# SparkFun_TEMT6000_Breakout-v12.net
KiCad netlist of a schematic drawn in EAGLE
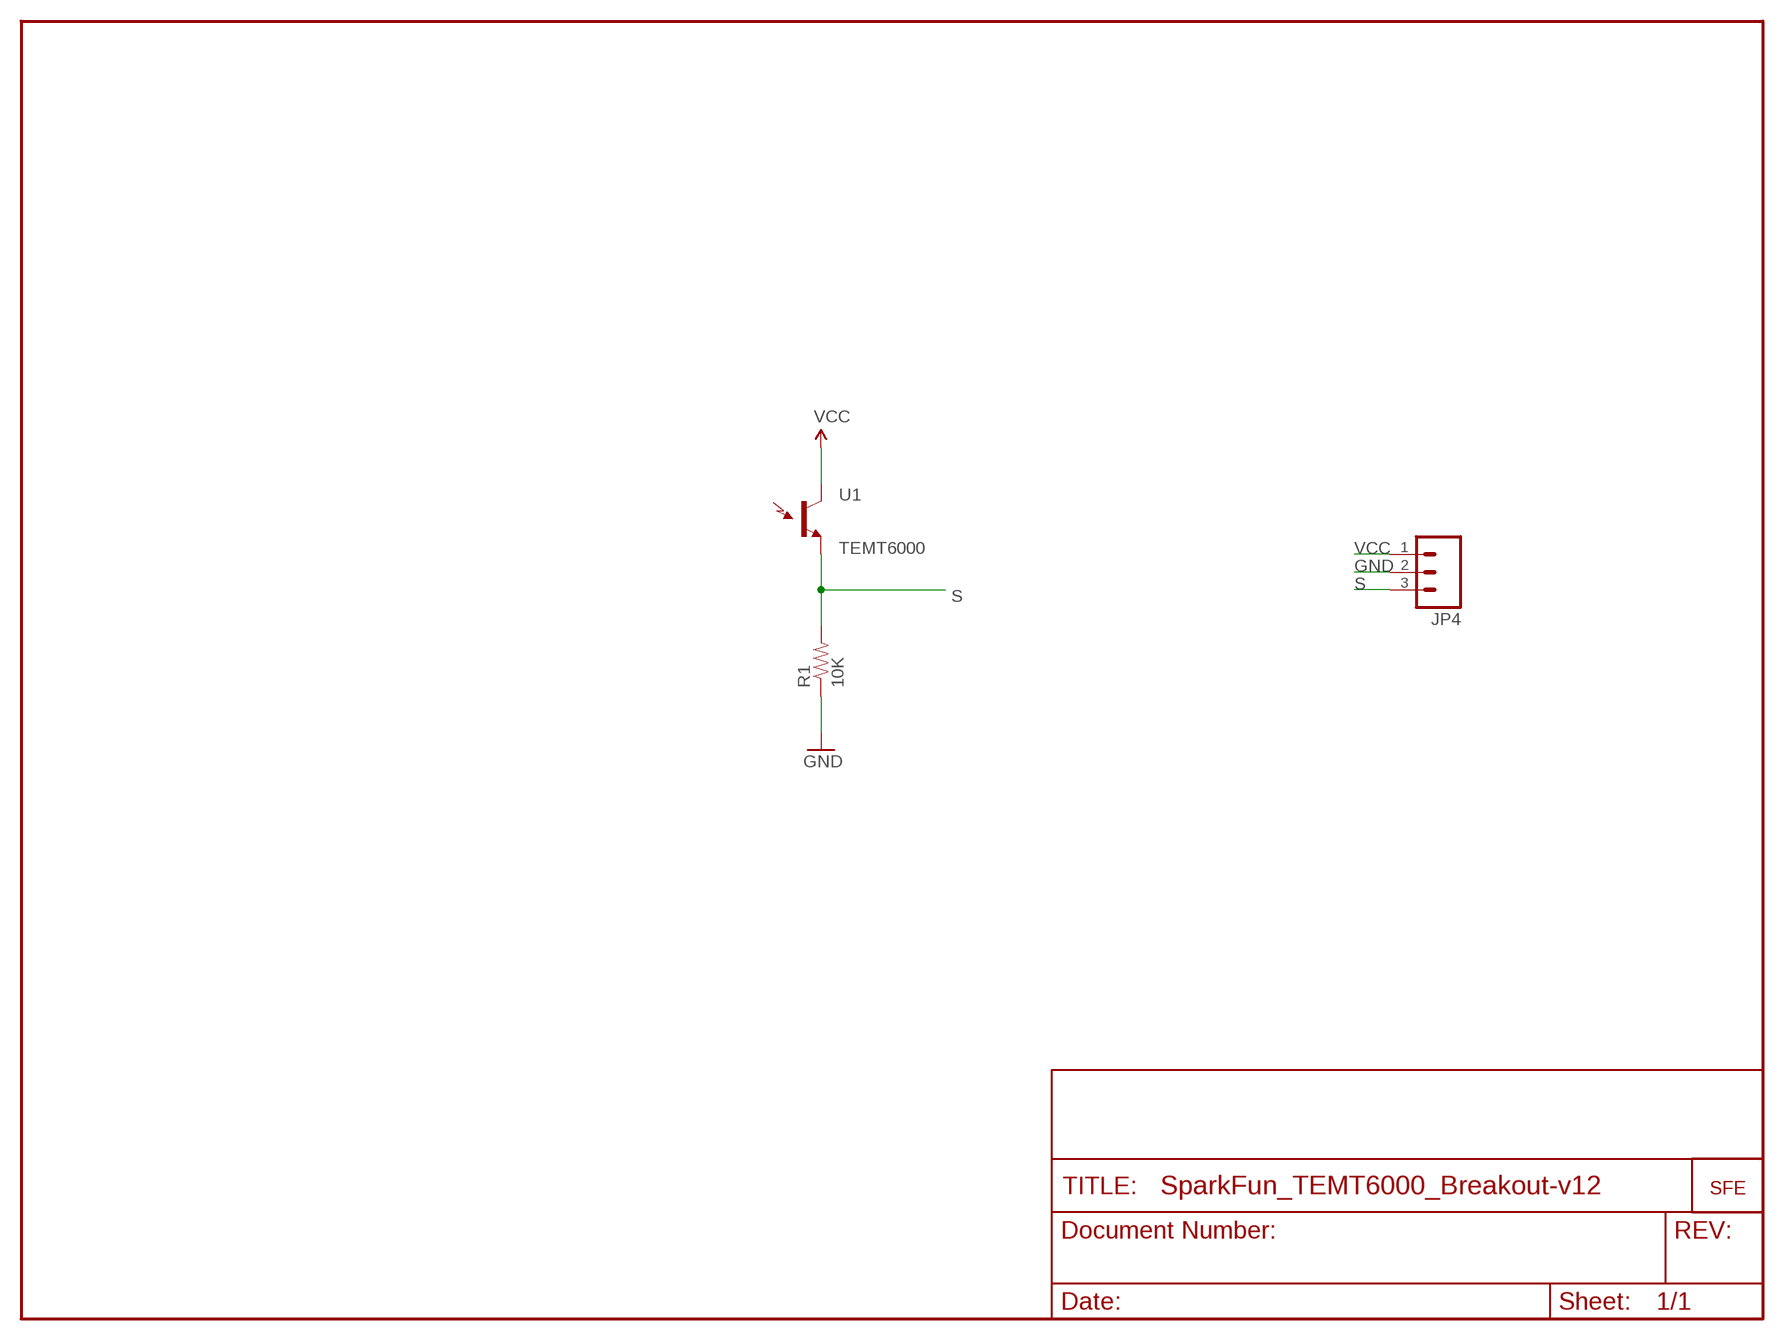
[diagram p0: schematic, sheet 1]

(export (version "E")
  (design (tool "Eeschema 10.0.6"))
  (components
    (comp (ref "JP4")
      (value "M03PTH")
      (footprint "eagle-import:1X03")
      (libsource (lib "eagle-import") (part "M03PTH"))
    )
    (comp (ref "R1")
      (value "10K")
      (footprint "eagle-import:0402-RES")
      (libsource (lib "eagle-import") (part "RESISTOR0402-RES"))
    )
    (comp (ref "U$1")
      (value "LOGO-SFESK")
      (footprint "eagle-import:SFE-LOGO-FLAME")
      (libsource (lib "eagle-import") (part "LOGO-SFESK"))
    )
    (comp (ref "U1")
      (value "TEMT6000")
      (footprint "eagle-import:TEMT6000-SEN")
      (libsource (lib "eagle-import") (part "TEMT6000"))
    )
  )
  (nets
    (net (code "1") (name "/S") (class "Default")
      (node (ref "JP4") (pin "3") (pinfunction "3_3") (pintype "passive"))
      (node (ref "R1") (pin "2") (pinfunction "2_2") (pintype "passive"))
      (node (ref "U1") (pin "EMITTER") (pinfunction "E1_EMITTER") (pintype "passive"))
    )
    (net (code "2") (name "GND") (class "Default")
      (node (ref "JP4") (pin "2") (pinfunction "2_2") (pintype "passive"))
      (node (ref "R1") (pin "1") (pinfunction "1_1") (pintype "passive"))
    )
    (net (code "3") (name "VCC") (class "Default")
      (node (ref "JP4") (pin "1") (pinfunction "1_1") (pintype "passive"))
      (node (ref "U1") (pin "COLLECTOR") (pinfunction "C1_COLLECTOR") (pintype "passive"))
    )
  )
)
